# boardShildSchematicbackup.net
KiCad netlist of a schematic drawn in EAGLE
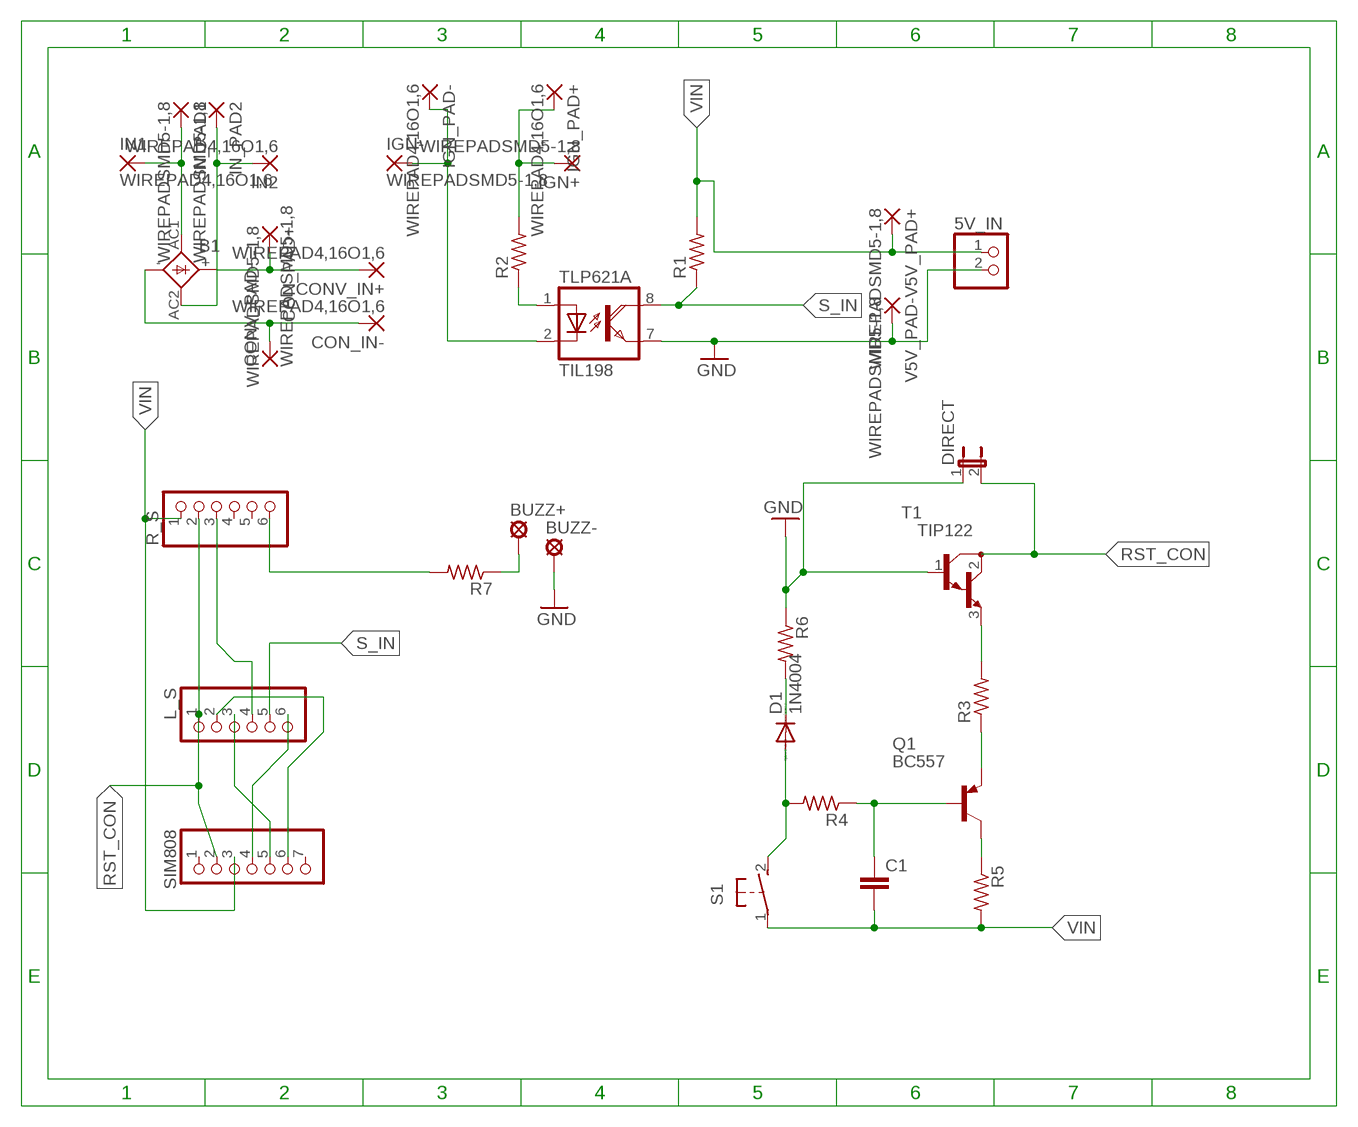
[diagram p0: schematic, sheet 1]

(export (version "E")
  (design (tool "Eeschema 10.0.6"))
  (components
    (comp (ref "5V_IN")
      (value "PINHD-1X2")
      (footprint "eagle-import:1X02")
      (libsource (lib "eagle-import") (part "PINHD-1X2"))
    )
    (comp (ref "B1")
      (value "FB15")
      (footprint "eagle-import:FB15")
      (libsource (lib "eagle-import") (part "FB15"))
    )
    (comp (ref "BUZZ+")
      (value "LSP10")
      (footprint "eagle-import:LSP10")
      (libsource (lib "eagle-import") (part "LSP10"))
    )
    (comp (ref "BUZZ-")
      (value "LSP10")
      (footprint "eagle-import:LSP10")
      (libsource (lib "eagle-import") (part "LSP10"))
    )
    (comp (ref "C1")
      (value "C2.5/5")
      (footprint "eagle-import:C2.5-5")
      (libsource (lib "eagle-import") (part "C2.5/5"))
    )
    (comp (ref "CONV_IN+")
      (value "WIREPAD4,16O1,6")
      (footprint "eagle-import:4,16O1,6")
      (libsource (lib "eagle-import") (part "WIREPAD4,16O1,6"))
    )
    (comp (ref "CONV_PAD-")
      (value "WIREPADSMD5-1,8")
      (footprint "eagle-import:5-1,8")
      (libsource (lib "eagle-import") (part "WIREPADSMD5-1,8"))
    )
    (comp (ref "CON_IN-")
      (value "WIREPAD4,16O1,6")
      (footprint "eagle-import:4,16O1,6")
      (libsource (lib "eagle-import") (part "WIREPAD4,16O1,6"))
    )
    (comp (ref "CON_PAD+")
      (value "WIREPADSMD5-1,8")
      (footprint "eagle-import:5-1,8")
      (libsource (lib "eagle-import") (part "WIREPADSMD5-1,8"))
    )
    (comp (ref "D1")
      (value "1N4004")
      (footprint "eagle-import:DO41-10")
      (libsource (lib "eagle-import") (part "1N4004"))
    )
    (comp (ref "DIRECT")
      (value "JP1E")
      (footprint "eagle-import:JP1")
      (libsource (lib "eagle-import") (part "JP1E"))
    )
    (comp (ref "IGN+")
      (value "WIREPADSMD5-1,8")
      (footprint "eagle-import:5-1,8")
      (libsource (lib "eagle-import") (part "WIREPADSMD5-1,8"))
    )
    (comp (ref "IGN-")
      (value "WIREPADSMD5-1,8")
      (footprint "eagle-import:5-1,8")
      (libsource (lib "eagle-import") (part "WIREPADSMD5-1,8"))
    )
    (comp (ref "IGN_PAD+")
      (value "WIREPAD4,16O1,6")
      (footprint "eagle-import:4,16O1,6")
      (libsource (lib "eagle-import") (part "WIREPAD4,16O1,6"))
    )
    (comp (ref "IGN_PAD-")
      (value "WIREPAD4,16O1,6")
      (footprint "eagle-import:4,16O1,6")
      (libsource (lib "eagle-import") (part "WIREPAD4,16O1,6"))
    )
    (comp (ref "IN1")
      (value "WIREPAD4,16O1,6")
      (footprint "eagle-import:4,16O1,6")
      (libsource (lib "eagle-import") (part "WIREPAD4,16O1,6"))
    )
    (comp (ref "IN2")
      (value "WIREPAD4,16O1,6")
      (footprint "eagle-import:4,16O1,6")
      (libsource (lib "eagle-import") (part "WIREPAD4,16O1,6"))
    )
    (comp (ref "IN_PAD1")
      (value "WIREPADSMD5-1,8")
      (footprint "eagle-import:5-1,8")
      (libsource (lib "eagle-import") (part "WIREPADSMD5-1,8"))
    )
    (comp (ref "IN_PAD2")
      (value "WIREPADSMD5-1,8")
      (footprint "eagle-import:5-1,8")
      (libsource (lib "eagle-import") (part "WIREPADSMD5-1,8"))
    )
    (comp (ref "L_S")
      (value "PINHD-1X6")
      (footprint "eagle-import:1X06")
      (libsource (lib "eagle-import") (part "PINHD-1X6"))
    )
    (comp (ref "Q1")
      (value "BC557")
      (footprint "eagle-import:TO92")
      (libsource (lib "eagle-import") (part "BC557"))
    )
    (comp (ref "R1")
      (value "R-US_0204/5")
      (footprint "eagle-import:0204_5")
      (libsource (lib "eagle-import") (part "R-US_0204/5"))
    )
    (comp (ref "R2")
      (value "R-US_0204/5")
      (footprint "eagle-import:0204_5")
      (libsource (lib "eagle-import") (part "R-US_0204/5"))
    )
    (comp (ref "R3")
      (value "R-US_0204/5")
      (footprint "eagle-import:0204_5")
      (libsource (lib "eagle-import") (part "R-US_0204/5"))
    )
    (comp (ref "R4")
      (value "R-US_0204/5")
      (footprint "eagle-import:0204_5")
      (libsource (lib "eagle-import") (part "R-US_0204/5"))
    )
    (comp (ref "R5")
      (value "R-US_0204/5")
      (footprint "eagle-import:0204_5")
      (libsource (lib "eagle-import") (part "R-US_0204/5"))
    )
    (comp (ref "R6")
      (value "R-US_0204/5")
      (footprint "eagle-import:0204_5")
      (libsource (lib "eagle-import") (part "R-US_0204/5"))
    )
    (comp (ref "R7")
      (value "R-US_0204/5")
      (footprint "eagle-import:0204_5")
      (libsource (lib "eagle-import") (part "R-US_0204/5"))
    )
    (comp (ref "R_S")
      (value "PINHD-1X6")
      (footprint "eagle-import:1X06")
      (libsource (lib "eagle-import") (part "PINHD-1X6"))
    )
    (comp (ref "S1")
      (value "31-XX")
      (footprint "eagle-import:B3F-31XX")
      (fields (field (name "MPN") "B3F-3100"))
      (libsource (lib "eagle-import") (part "31-XX"))
    )
    (comp (ref "SIM808")
      (value "PINHD-1X7")
      (footprint "eagle-import:1X07")
      (libsource (lib "eagle-import") (part "PINHD-1X7"))
    )
    (comp (ref "T1")
      (value "TIP122")
      (footprint "eagle-import:TO220")
      (libsource (lib "eagle-import") (part "TIP122"))
    )
    (comp (ref "TLP621")
      (value "TIL198")
      (footprint "eagle-import:DIL08")
      (libsource (lib "eagle-import") (part "TIL198"))
    )
    (comp (ref "V5V_PAD+")
      (value "WIREPADSMD5-1,8")
      (footprint "eagle-import:5-1,8")
      (libsource (lib "eagle-import") (part "WIREPADSMD5-1,8"))
    )
    (comp (ref "V5V_PAD-")
      (value "WIREPADSMD5-1,8")
      (footprint "eagle-import:5-1,8")
      (libsource (lib "eagle-import") (part "WIREPADSMD5-1,8"))
    )
  )
  (nets
    (net (code "1") (name "GND") (class "Default")
      (node (ref "5V_IN") (pin "2") (pinfunction "2_2") (pintype "passive"))
      (node (ref "BUZZ-") (pin "MP") (pinfunction "MP_MP") (pintype "passive"))
      (node (ref "DIRECT") (pin "1") (pinfunction "1_1") (pintype "passive"))
      (node (ref "R6") (pin "1") (pinfunction "1_1") (pintype "passive"))
      (node (ref "T1") (pin "1") (pinfunction "B_1") (pintype "passive"))
      (node (ref "TLP621") (pin "7") (pinfunction "EMI_7") (pintype "passive"))
      (node (ref "V5V_PAD-") (pin "1") (pinfunction "P_1") (pintype "passive"))
    )
    (net (code "2") (name "Net-(BUZZ+-PadMP)") (class "Default")
      (node (ref "BUZZ+") (pin "MP") (pinfunction "MP_MP") (pintype "passive"))
      (node (ref "R7") (pin "1") (pinfunction "1_1") (pintype "passive"))
    )
    (net (code "3") (name "Net-(CONV_IN+-P)") (class "Default")
      (node (ref "B1") (pin "+") (pinfunction "+_+") (pintype "passive"))
      (node (ref "CONV_IN+") (pin "1") (pinfunction "P_1") (pintype "passive"))
      (node (ref "CON_PAD+") (pin "1") (pinfunction "P_1") (pintype "passive"))
    )
    (net (code "4") (name "Net-(CONV_PAD--P)") (class "Default")
      (node (ref "B1") (pin "-") (pinfunction "-_-") (pintype "passive"))
      (node (ref "CONV_PAD-") (pin "1") (pinfunction "P_1") (pintype "passive"))
      (node (ref "CON_IN-") (pin "1") (pinfunction "P_1") (pintype "passive"))
    )
    (net (code "5") (name "Net-(D1-PadC)") (class "Default")
      (node (ref "D1") (pin "C") (pinfunction "C_C") (pintype "passive"))
      (node (ref "R6") (pin "2") (pinfunction "2_2") (pintype "passive"))
    )
    (net (code "6") (name "Net-(IGN+-P)") (class "Default")
      (node (ref "IGN+") (pin "1") (pinfunction "P_1") (pintype "passive"))
      (node (ref "IGN_PAD+") (pin "1") (pinfunction "P_1") (pintype "passive"))
      (node (ref "R2") (pin "2") (pinfunction "2_2") (pintype "passive"))
    )
    (net (code "7") (name "Net-(IGN--P)") (class "Default")
      (node (ref "IGN-") (pin "1") (pinfunction "P_1") (pintype "passive"))
      (node (ref "IGN_PAD-") (pin "1") (pinfunction "P_1") (pintype "passive"))
      (node (ref "TLP621") (pin "2") (pinfunction "C_2") (pintype "passive"))
    )
    (net (code "8") (name "Net-(IN1-P)") (class "Default")
      (node (ref "B1") (pin "AC1") (pinfunction "AC1_AC1") (pintype "passive"))
      (node (ref "IN1") (pin "1") (pinfunction "P_1") (pintype "passive"))
      (node (ref "IN_PAD1") (pin "1") (pinfunction "P_1") (pintype "passive"))
    )
    (net (code "9") (name "Net-(IN2-P)") (class "Default")
      (node (ref "B1") (pin "AC2") (pinfunction "AC2_AC2") (pintype "passive"))
      (node (ref "IN2") (pin "1") (pinfunction "P_1") (pintype "passive"))
      (node (ref "IN_PAD2") (pin "1") (pinfunction "P_1") (pintype "passive"))
    )
    (net (code "10") (name "Net-(L_S-Pad2)") (class "Default")
      (node (ref "L_S") (pin "2") (pinfunction "2_2") (pintype "passive"))
      (node (ref "SIM808") (pin "6") (pinfunction "6_6") (pintype "passive"))
    )
    (net (code "11") (name "Net-(L_S-Pad3)") (class "Default")
      (node (ref "L_S") (pin "3") (pinfunction "3_3") (pintype "passive"))
      (node (ref "SIM808") (pin "5") (pinfunction "5_5") (pintype "passive"))
    )
    (net (code "12") (name "Net-(L_S-Pad4)") (class "Default")
      (node (ref "L_S") (pin "4") (pinfunction "4_4") (pintype "passive"))
      (node (ref "R_S") (pin "3") (pinfunction "3_3") (pintype "passive"))
    )
    (net (code "13") (name "Net-(L_S-Pad6)") (class "Default")
      (node (ref "L_S") (pin "6") (pinfunction "6_6") (pintype "passive"))
      (node (ref "SIM808") (pin "4") (pinfunction "4_4") (pintype "passive"))
    )
    (net (code "14") (name "Net-(Q1-B)") (class "Default")
      (node (ref "C1") (pin "1") (pinfunction "1_1") (pintype "passive"))
      (node (ref "Q1") (pin "2") (pinfunction "B_2") (pintype "passive"))
      (node (ref "R4") (pin "1") (pinfunction "1_1") (pintype "passive"))
    )
    (net (code "15") (name "Net-(Q1-C)") (class "Default")
      (node (ref "Q1") (pin "3") (pinfunction "C_3") (pintype "passive"))
      (node (ref "R5") (pin "1") (pinfunction "1_1") (pintype "passive"))
    )
    (net (code "16") (name "Net-(Q1-E)") (class "Default")
      (node (ref "Q1") (pin "1") (pinfunction "E_1") (pintype "passive"))
      (node (ref "R3") (pin "1") (pinfunction "1_1") (pintype "passive"))
    )
    (net (code "17") (name "Net-(R7-Pad2)") (class "Default")
      (node (ref "R7") (pin "2") (pinfunction "2_2") (pintype "passive"))
      (node (ref "R_S") (pin "6") (pinfunction "6_6") (pintype "passive"))
    )
    (net (code "18") (name "Net-(S1-S)") (class "Default")
      (node (ref "D1") (pin "A") (pinfunction "A_A") (pintype "passive"))
      (node (ref "R4") (pin "2") (pinfunction "2_2") (pintype "passive"))
      (node (ref "S1") (pin "2") (pinfunction "S_2") (pintype "passive"))
    )
    (net (code "19") (name "Net-(T1-E)") (class "Default")
      (node (ref "R3") (pin "2") (pinfunction "2_2") (pintype "passive"))
      (node (ref "T1") (pin "3") (pinfunction "E_3") (pintype "passive"))
    )
    (net (code "20") (name "Net-(TLP621A-A)") (class "Default")
      (node (ref "R2") (pin "1") (pinfunction "1_1") (pintype "passive"))
      (node (ref "TLP621") (pin "1") (pinfunction "A_1") (pintype "passive"))
    )
    (net (code "21") (name "RST_CON") (class "Default")
      (node (ref "DIRECT") (pin "2") (pinfunction "2_2") (pintype "passive"))
      (node (ref "L_S") (pin "1") (pinfunction "1_1") (pintype "passive"))
      (node (ref "R_S") (pin "2") (pinfunction "2_2") (pintype "passive"))
      (node (ref "SIM808") (pin "2") (pinfunction "2_2") (pintype "passive"))
      (node (ref "T1") (pin "2") (pinfunction "C_2") (pintype "passive"))
    )
    (net (code "22") (name "S_IN") (class "Default")
      (node (ref "L_S") (pin "5") (pinfunction "5_5") (pintype "passive"))
      (node (ref "R1") (pin "1") (pinfunction "1_1") (pintype "passive"))
      (node (ref "TLP621") (pin "8") (pinfunction "COL_8") (pintype "passive"))
    )
    (net (code "23") (name "VIN") (class "Default")
      (node (ref "5V_IN") (pin "1") (pinfunction "1_1") (pintype "passive"))
      (node (ref "C1") (pin "2") (pinfunction "2_2") (pintype "passive"))
      (node (ref "R1") (pin "2") (pinfunction "2_2") (pintype "passive"))
      (node (ref "R5") (pin "2") (pinfunction "2_2") (pintype "passive"))
      (node (ref "R_S") (pin "1") (pinfunction "1_1") (pintype "passive"))
      (node (ref "S1") (pin "1") (pinfunction "P_1") (pintype "passive"))
      (node (ref "SIM808") (pin "3") (pinfunction "3_3") (pintype "passive"))
      (node (ref "V5V_PAD+") (pin "1") (pinfunction "P_1") (pintype "passive"))
    )
    (net (code "24") (name "unconnected-(R_S-Pad4)") (class "Default")
      (node (ref "R_S") (pin "4") (pinfunction "4_4") (pintype "passive"))
    )
    (net (code "25") (name "unconnected-(R_S-Pad5)") (class "Default")
      (node (ref "R_S") (pin "5") (pinfunction "5_5") (pintype "passive"))
    )
    (net (code "26") (name "unconnected-(SIM808-Pad1)") (class "Default")
      (node (ref "SIM808") (pin "1") (pinfunction "1_1") (pintype "passive"))
    )
    (net (code "27") (name "unconnected-(SIM808-Pad7)") (class "Default")
      (node (ref "SIM808") (pin "7") (pinfunction "7_7") (pintype "passive"))
    )
  )
)
